# PI_SCH_HDMI.net
KiCad netlist of a schematic drawn in EasyEDA
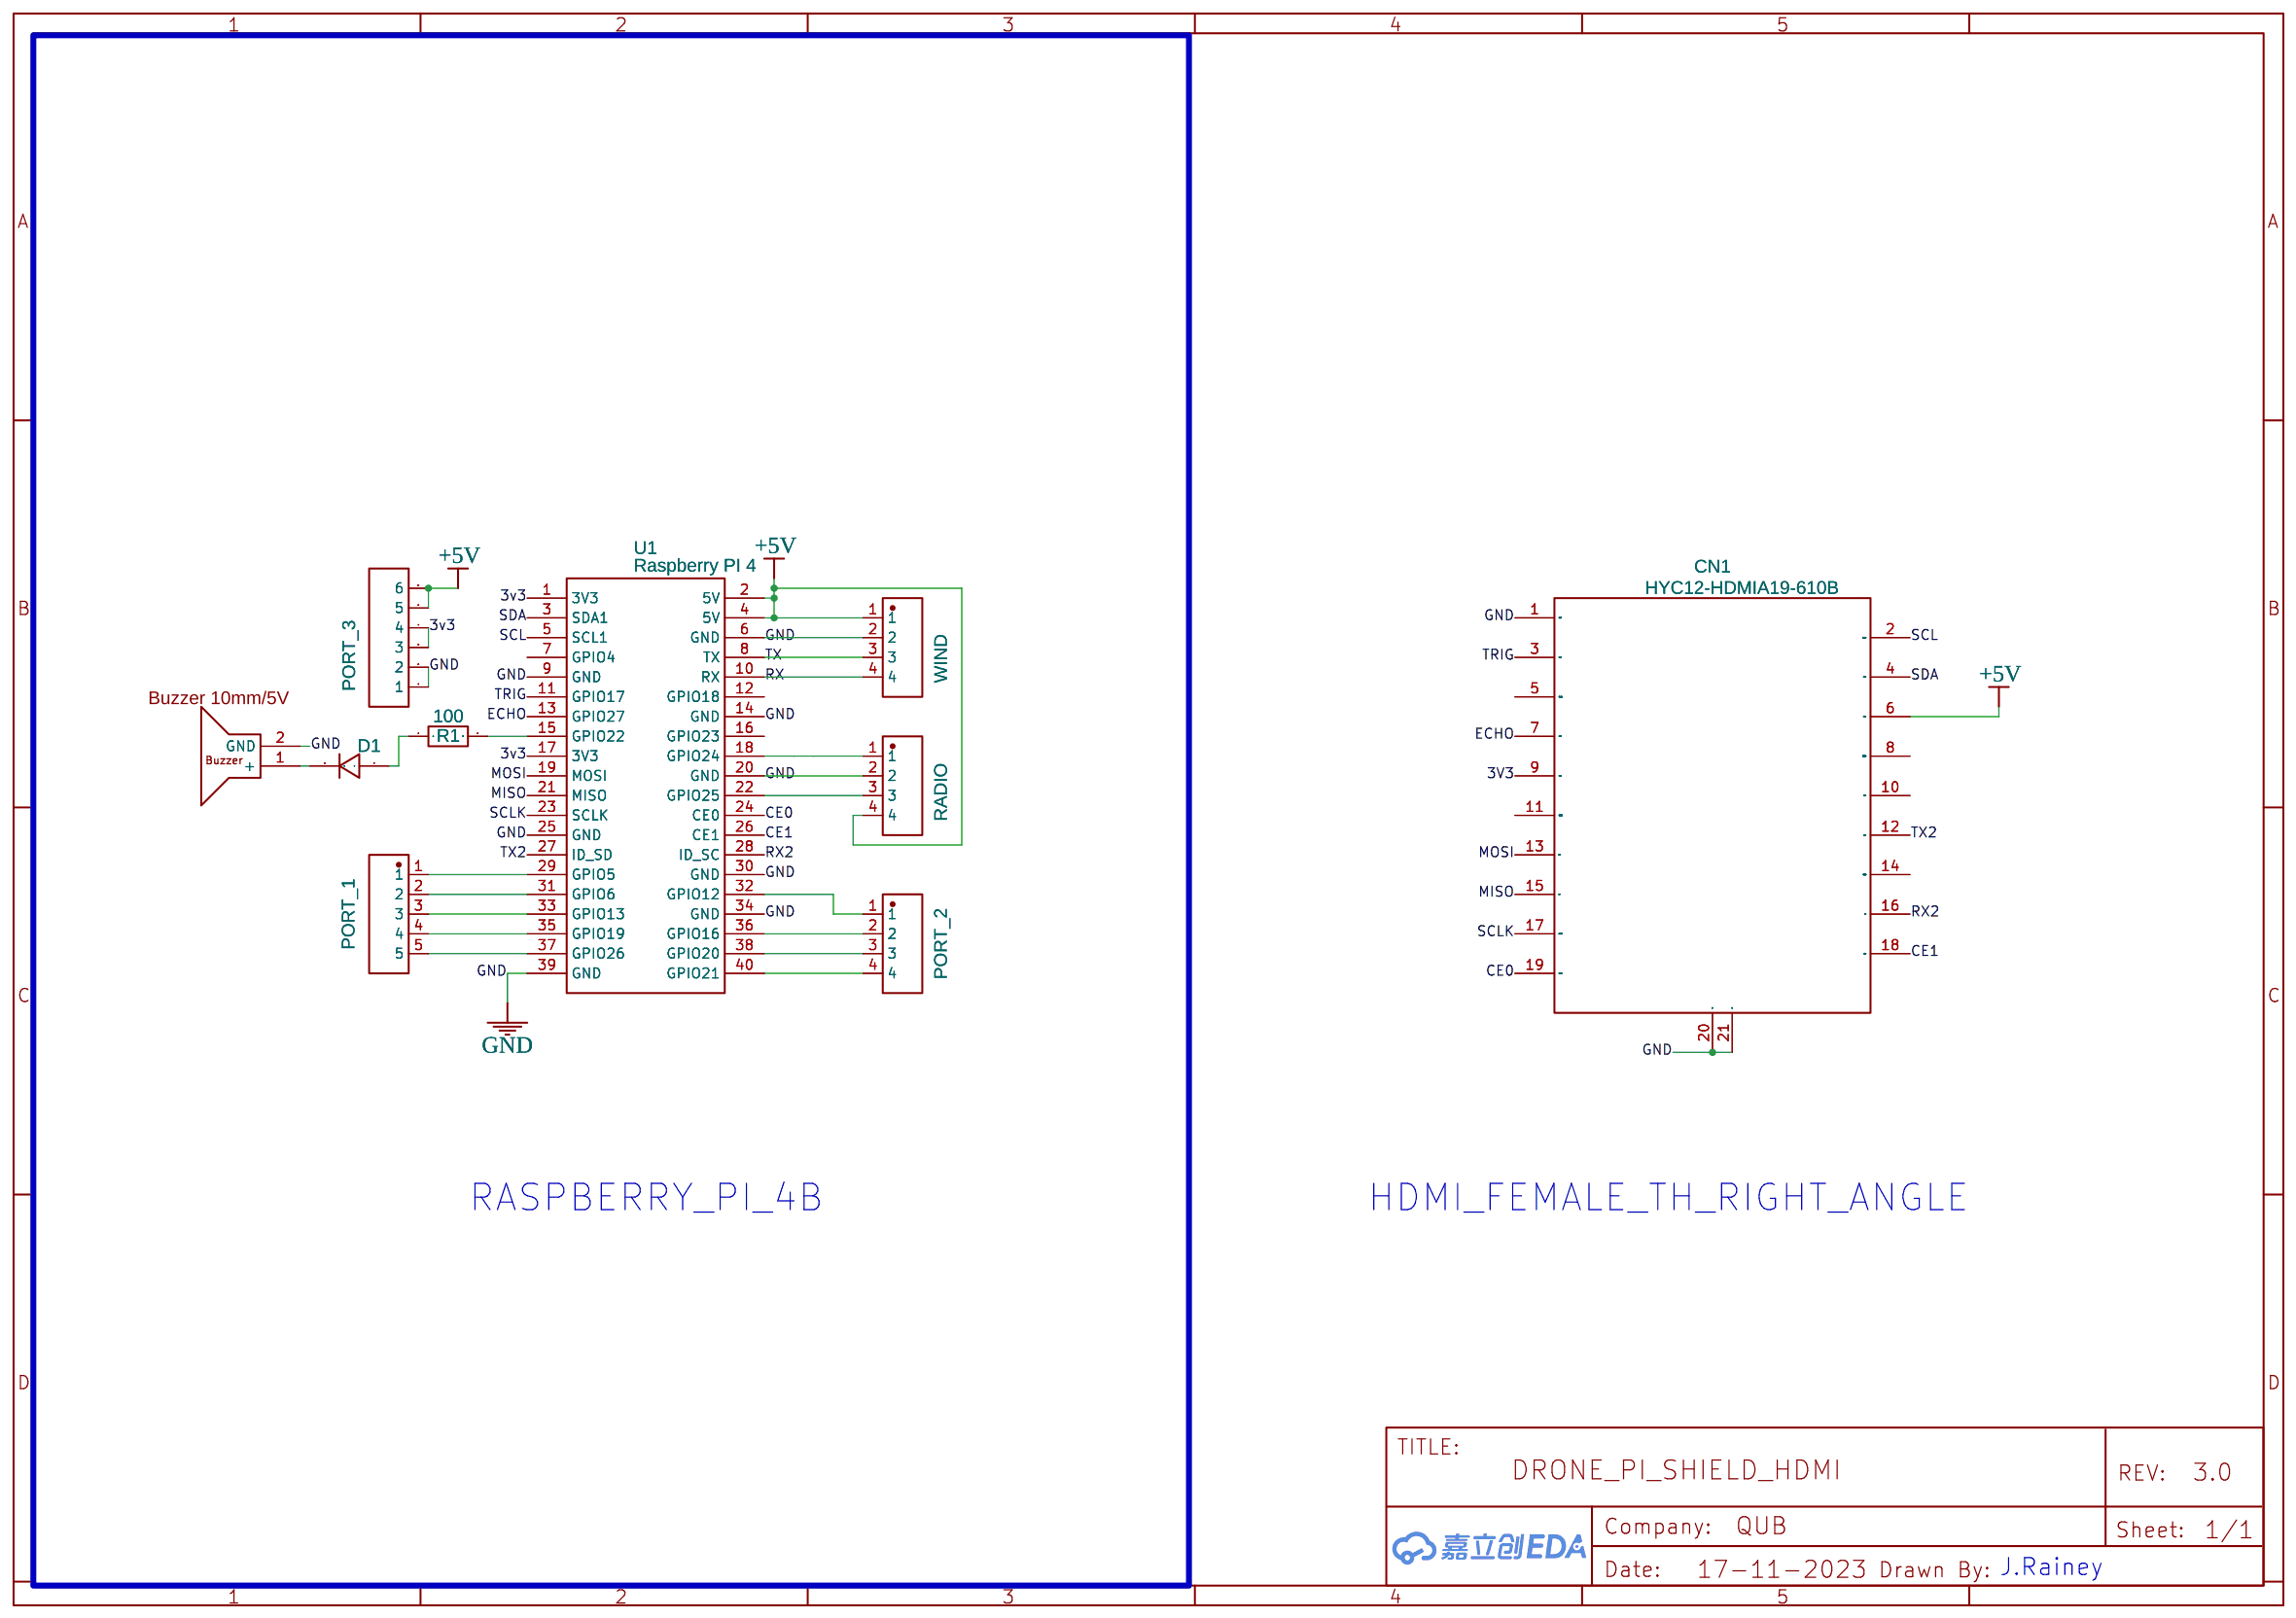
[diagram p0: schematic sheet]

(export (version "E")
  (design (tool "Eeschema 10.0.6"))
  (components
    (comp (ref "BUZZER1")
      (value "Buzzer 10mm/5V")
      (fields (field (name "BOM_Manufacturer Part") "BUZZER"))
      (libsource (lib "") (part "Buzzer 10mm/5V"))
    )
    (comp (ref "CN1")
      (value "HYC12-HDMIA19-610B")
      (fields (field (name "BOM_Supplier Part") "C711354"))
      (libsource (lib "") (part "HYC12-HDMIA19-610B"))
    )
    (comp (ref "D1")
      (value "1N4448")
      (fields (field (name "Manufacturer") "ST(先科)"))
      (libsource (lib "") (part "1N4448"))
    )
    (comp (ref "PORT_1")
      (value "PZ254V-11-05P")
      (fields (field (name "BOM_Supplier Part") "C492404"))
      (libsource (lib "") (part "PZ254V-11-05P"))
    )
    (comp (ref "PORT_2")
      (value "PZ254V-11-04P")
      (fields (field (name "BOM_Supplier Part") "C492403"))
      (libsource (lib "") (part "PZ254V-11-04P"))
    )
    (comp (ref "PORT_3")
      (value "HEADER-MALE-2.54_1X6")
      (fields
        (field (name "BOM_Manufacturer Part") "Header-Male-2.54_1x6")
        (field (name "BOM_Supplier Part") "C37208")
      )
      (libsource (lib "") (part "HEADER-MALE-2.54_1X6"))
    )
    (comp (ref "R1") (value "100") (libsource (lib "") (part "R_AXIAL-0.4_EU")))
    (comp (ref "RADIO")
      (value "PZ254V-11-04P")
      (fields (field (name "BOM_Supplier Part") "C492403"))
      (libsource (lib "") (part "PZ254V-11-04P_1"))
    )
    (comp (ref "U1") (value "Raspberry PI 4") (libsource (lib "") (part "Raspberry PI 4")))
    (comp (ref "WIND")
      (value "PZ254V-11-04P")
      (fields (field (name "BOM_Supplier Part") "C492403"))
      (libsource (lib "") (part "PZ254V-11-04P_2"))
    )
  )
  (nets
    (net (code "1") (name "+5V") (class "Default")
      (node (ref "CN1") (pin "6") (pinfunction "TMDS_Data_1-_6") (pintype "unspecified"))
      (node (ref "PORT_3") (pin "5") (pinfunction "5_5") (pintype "input"))
      (node (ref "PORT_3") (pin "6") (pinfunction "6_6") (pintype "input"))
      (node (ref "RADIO") (pin "4") (pinfunction "4_4") (pintype "unspecified"))
      (node (ref "U1") (pin "2") (pinfunction "5V_2") (pintype "unspecified"))
      (node (ref "U1") (pin "4") (pinfunction "5V_4") (pintype "unspecified"))
      (node (ref "WIND") (pin "1") (pinfunction "1_1") (pintype "unspecified"))
    )
    (net (code "2") (name "/3V3") (class "Default")
      (node (ref "CN1") (pin "9") (pinfunction "TMDS_Data_0-_9") (pintype "unspecified"))
    )
    (net (code "3") (name "/3v3") (class "Default")
      (node (ref "PORT_3") (pin "3") (pinfunction "3_3") (pintype "input"))
      (node (ref "PORT_3") (pin "4") (pinfunction "4_4") (pintype "input"))
      (node (ref "U1") (pin "1") (pinfunction "3V3_1") (pintype "unspecified"))
      (node (ref "U1") (pin "17") (pinfunction "3V3_17") (pintype "unspecified"))
    )
    (net (code "4") (name "/CE0") (class "Default")
      (node (ref "CN1") (pin "19") (pinfunction "Hot_Plug_Detect_19") (pintype "unspecified"))
      (node (ref "U1") (pin "24") (pinfunction "CE0_24") (pintype "unspecified"))
    )
    (net (code "5") (name "/CE1") (class "Default")
      (node (ref "CN1") (pin "18") (pinfunction "+5V_Power_18") (pintype "unspecified"))
      (node (ref "U1") (pin "26") (pinfunction "CE1_26") (pintype "unspecified"))
    )
    (net (code "6") (name "/ECHO") (class "Default")
      (node (ref "CN1") (pin "7") (pinfunction "TMDS_Data_0+_7") (pintype "unspecified"))
      (node (ref "U1") (pin "13") (pinfunction "GPIO27_13") (pintype "unspecified"))
    )
    (net (code "7") (name "/MISO") (class "Default")
      (node (ref "CN1") (pin "15") (pinfunction "SCL_15") (pintype "unspecified"))
      (node (ref "U1") (pin "21") (pinfunction "MISO_21") (pintype "unspecified"))
    )
    (net (code "8") (name "/MOSI") (class "Default")
      (node (ref "CN1") (pin "13") (pinfunction "CEC_13") (pintype "unspecified"))
      (node (ref "U1") (pin "19") (pinfunction "MOSI_19") (pintype "unspecified"))
    )
    (net (code "9") (name "/RX") (class "Default")
      (node (ref "U1") (pin "10") (pinfunction "RX_10") (pintype "unspecified"))
      (node (ref "WIND") (pin "4") (pinfunction "4_4") (pintype "unspecified"))
    )
    (net (code "10") (name "/RX2") (class "Default")
      (node (ref "CN1") (pin "16") (pinfunction "SDA_16") (pintype "unspecified"))
      (node (ref "U1") (pin "28") (pinfunction "ID_SC_28") (pintype "unspecified"))
    )
    (net (code "11") (name "/SCL") (class "Default")
      (node (ref "CN1") (pin "2") (pinfunction "TMDS_Data_2_Shield_2") (pintype "unspecified"))
      (node (ref "U1") (pin "5") (pinfunction "SCL1_5") (pintype "unspecified"))
    )
    (net (code "12") (name "/SCLK") (class "Default")
      (node (ref "CN1") (pin "17") (pinfunction "DDC/CEC_Ground_17") (pintype "unspecified"))
      (node (ref "U1") (pin "23") (pinfunction "SCLK_23") (pintype "unspecified"))
    )
    (net (code "13") (name "/SDA") (class "Default")
      (node (ref "CN1") (pin "4") (pinfunction "TMDS_Data_1+_4") (pintype "unspecified"))
      (node (ref "U1") (pin "3") (pinfunction "SDA1_3") (pintype "unspecified"))
    )
    (net (code "14") (name "/TRIG") (class "Default")
      (node (ref "CN1") (pin "3") (pinfunction "TMDS_Data_2-_3") (pintype "unspecified"))
      (node (ref "U1") (pin "11") (pinfunction "GPIO17_11") (pintype "unspecified"))
    )
    (net (code "15") (name "/TX") (class "Default")
      (node (ref "U1") (pin "8") (pinfunction "TX_8") (pintype "unspecified"))
      (node (ref "WIND") (pin "3") (pinfunction "3_3") (pintype "unspecified"))
    )
    (net (code "16") (name "/TX2") (class "Default")
      (node (ref "CN1") (pin "12") (pinfunction "TMDS_Clock-_12") (pintype "unspecified"))
      (node (ref "U1") (pin "27") (pinfunction "ID_SD_27") (pintype "unspecified"))
    )
    (net (code "17") (name "GND") (class "Default")
      (node (ref "BUZZER1") (pin "2") (pinfunction "GND_2") (pintype "unspecified"))
      (node (ref "CN1") (pin "1") (pinfunction "TMDS_Data_2+_1") (pintype "unspecified"))
      (node (ref "CN1") (pin "20") (pinfunction "EH_20") (pintype "unspecified"))
      (node (ref "CN1") (pin "21") (pinfunction "EH_21") (pintype "unspecified"))
      (node (ref "PORT_3") (pin "1") (pinfunction "1_1") (pintype "input"))
      (node (ref "PORT_3") (pin "2") (pinfunction "2_2") (pintype "input"))
      (node (ref "RADIO") (pin "2") (pinfunction "2_2") (pintype "unspecified"))
      (node (ref "U1") (pin "14") (pinfunction "GND_14") (pintype "unspecified"))
      (node (ref "U1") (pin "20") (pinfunction "GND_20") (pintype "unspecified"))
      (node (ref "U1") (pin "25") (pinfunction "GND_25") (pintype "unspecified"))
      (node (ref "U1") (pin "30") (pinfunction "GND_30") (pintype "unspecified"))
      (node (ref "U1") (pin "34") (pinfunction "GND_34") (pintype "unspecified"))
      (node (ref "U1") (pin "39") (pinfunction "GND_39") (pintype "unspecified"))
      (node (ref "U1") (pin "6") (pinfunction "GND_6") (pintype "unspecified"))
      (node (ref "U1") (pin "9") (pinfunction "GND_9") (pintype "unspecified"))
      (node (ref "WIND") (pin "2") (pinfunction "2_2") (pintype "unspecified"))
    )
    (net (code "18") (name "Net-(BUZZER1-+)") (class "Default")
      (node (ref "BUZZER1") (pin "1") (pinfunction "+_1") (pintype "unspecified"))
      (node (ref "D1") (pin "2") (pinfunction "K_2") (pintype "unspecified"))
    )
    (net (code "19") (name "Net-(D1-A)") (class "Default")
      (node (ref "D1") (pin "1") (pinfunction "A_1") (pintype "unspecified"))
      (node (ref "R1") (pin "1") (pinfunction "1_1") (pintype "unspecified"))
    )
    (net (code "20") (name "Net-(U1-GPIO5)") (class "Default")
      (node (ref "PORT_1") (pin "1") (pinfunction "1_1") (pintype "unspecified"))
      (node (ref "U1") (pin "29") (pinfunction "GPIO5_29") (pintype "unspecified"))
    )
    (net (code "21") (name "Net-(U1-GPIO6)") (class "Default")
      (node (ref "PORT_1") (pin "2") (pinfunction "2_2") (pintype "unspecified"))
      (node (ref "U1") (pin "31") (pinfunction "GPIO6_31") (pintype "unspecified"))
    )
    (net (code "22") (name "Net-(U1-GPIO12)") (class "Default")
      (node (ref "PORT_2") (pin "1") (pinfunction "1_1") (pintype "unspecified"))
      (node (ref "U1") (pin "32") (pinfunction "GPIO12_32") (pintype "unspecified"))
    )
    (net (code "23") (name "Net-(U1-GPIO13)") (class "Default")
      (node (ref "PORT_1") (pin "3") (pinfunction "3_3") (pintype "unspecified"))
      (node (ref "U1") (pin "33") (pinfunction "GPIO13_33") (pintype "unspecified"))
    )
    (net (code "24") (name "Net-(U1-GPIO16)") (class "Default")
      (node (ref "PORT_2") (pin "2") (pinfunction "2_2") (pintype "unspecified"))
      (node (ref "U1") (pin "36") (pinfunction "GPIO16_36") (pintype "unspecified"))
    )
    (net (code "25") (name "Net-(U1-GPIO19)") (class "Default")
      (node (ref "PORT_1") (pin "4") (pinfunction "4_4") (pintype "unspecified"))
      (node (ref "U1") (pin "35") (pinfunction "GPIO19_35") (pintype "unspecified"))
    )
    (net (code "26") (name "Net-(U1-GPIO20)") (class "Default")
      (node (ref "PORT_2") (pin "3") (pinfunction "3_3") (pintype "unspecified"))
      (node (ref "U1") (pin "38") (pinfunction "GPIO20_38") (pintype "unspecified"))
    )
    (net (code "27") (name "Net-(U1-GPIO21)") (class "Default")
      (node (ref "PORT_2") (pin "4") (pinfunction "4_4") (pintype "unspecified"))
      (node (ref "U1") (pin "40") (pinfunction "GPIO21_40") (pintype "unspecified"))
    )
    (net (code "28") (name "Net-(U1-GPIO22)") (class "Default")
      (node (ref "R1") (pin "2") (pinfunction "2_2") (pintype "unspecified"))
      (node (ref "U1") (pin "15") (pinfunction "GPIO22_15") (pintype "unspecified"))
    )
    (net (code "29") (name "Net-(U1-GPIO24)") (class "Default")
      (node (ref "RADIO") (pin "1") (pinfunction "1_1") (pintype "unspecified"))
      (node (ref "U1") (pin "18") (pinfunction "GPIO24_18") (pintype "unspecified"))
    )
    (net (code "30") (name "Net-(U1-GPIO25)") (class "Default")
      (node (ref "RADIO") (pin "3") (pinfunction "3_3") (pintype "unspecified"))
      (node (ref "U1") (pin "22") (pinfunction "GPIO25_22") (pintype "unspecified"))
    )
    (net (code "31") (name "Net-(U1-GPIO26)") (class "Default")
      (node (ref "PORT_1") (pin "5") (pinfunction "5_5") (pintype "unspecified"))
      (node (ref "U1") (pin "37") (pinfunction "GPIO26_37") (pintype "unspecified"))
    )
    (net (code "32") (name "unconnected-(CN1-Reserved_(N.C.)-Pad14)") (class "Default")
      (node (ref "CN1") (pin "14") (pinfunction "Reserved_(N.C.)_14") (pintype "unspecified"))
    )
    (net (code "33") (name "unconnected-(CN1-TMDS_Clock+-Pad10)") (class "Default")
      (node (ref "CN1") (pin "10") (pinfunction "TMDS_Clock+_10") (pintype "unspecified"))
    )
    (net (code "34") (name "unconnected-(CN1-TMDS_Clock_Shield-Pad11)") (class "Default")
      (node (ref "CN1") (pin "11") (pinfunction "TMDS_Clock_Shield_11") (pintype "unspecified"))
    )
    (net (code "35") (name "unconnected-(CN1-TMDS_Data_0_Shield-Pad8)") (class "Default")
      (node (ref "CN1") (pin "8") (pinfunction "TMDS_Data_0_Shield_8") (pintype "unspecified"))
    )
    (net (code "36") (name "unconnected-(CN1-TMDS_Data_1_Shield-Pad5)") (class "Default")
      (node (ref "CN1") (pin "5") (pinfunction "TMDS_Data_1_Shield_5") (pintype "unspecified"))
    )
    (net (code "37") (name "unconnected-(U1-GPIO4-Pad7)") (class "Default")
      (node (ref "U1") (pin "7") (pinfunction "GPIO4_7") (pintype "unspecified"))
    )
    (net (code "38") (name "unconnected-(U1-GPIO18-Pad12)") (class "Default")
      (node (ref "U1") (pin "12") (pinfunction "GPIO18_12") (pintype "unspecified"))
    )
    (net (code "39") (name "unconnected-(U1-GPIO23-Pad16)") (class "Default")
      (node (ref "U1") (pin "16") (pinfunction "GPIO23_16") (pintype "unspecified"))
    )
  )
)
